# 01_Power_Control.net
KiCad netlist of a schematic drawn in Altium Designer
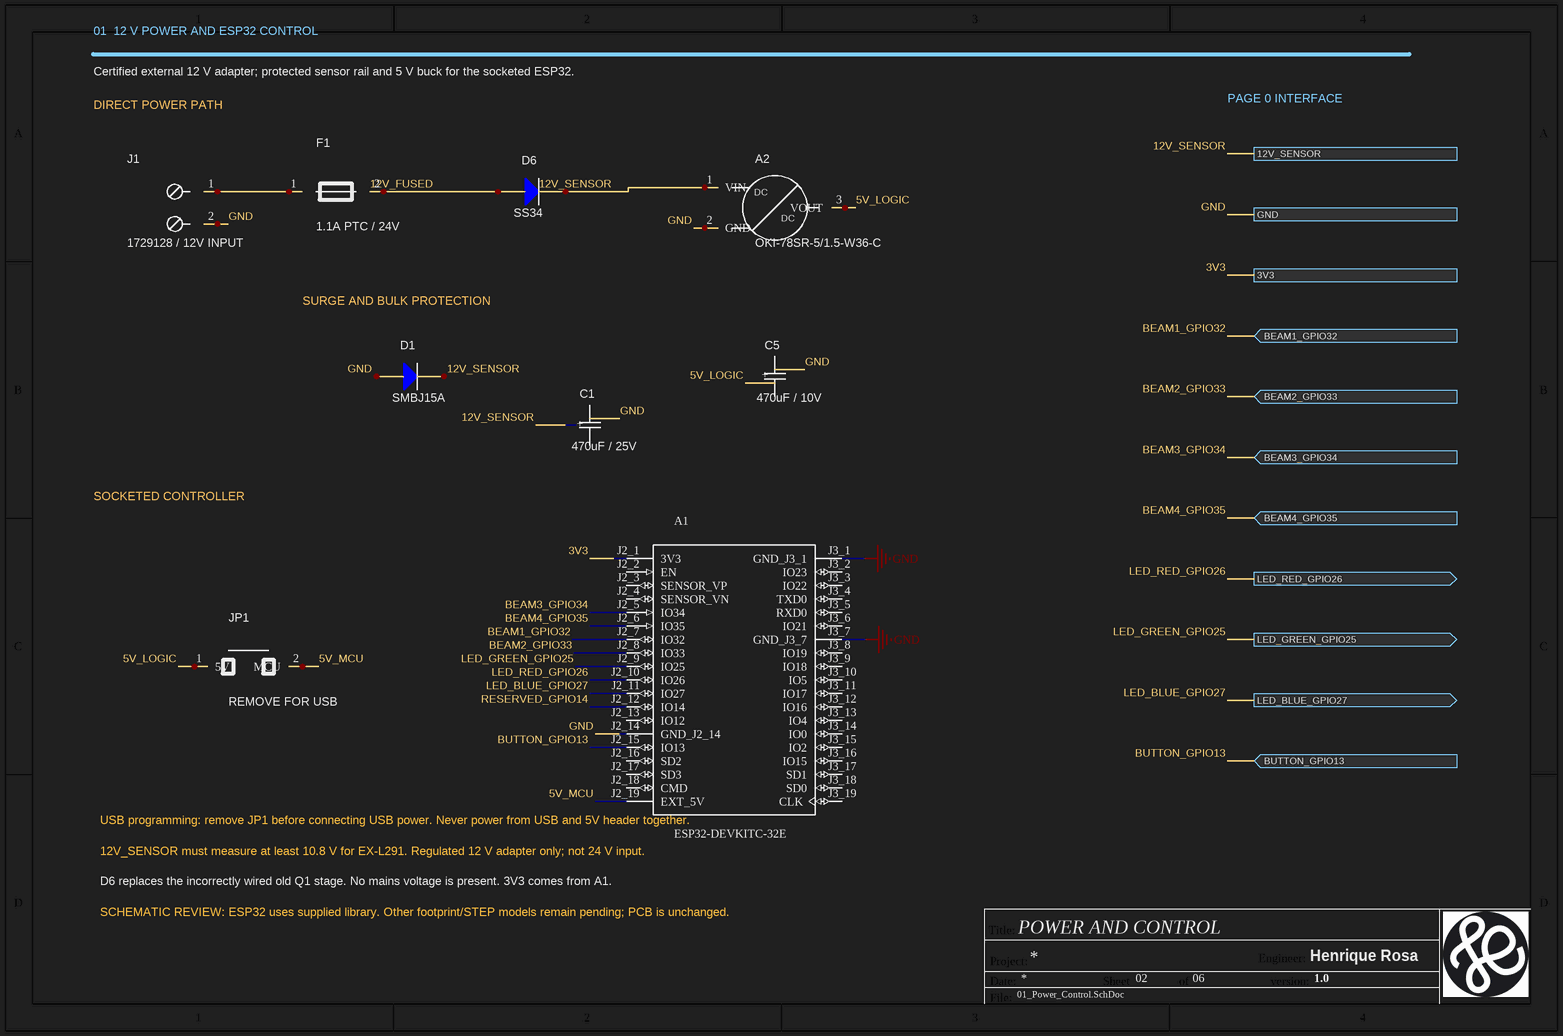
[diagram p0: 01_Power_Control.SchDoc]

(export (version "E")
  (design (tool "Eeschema 10.0.6"))
  (components
    (comp (ref "A1")
      (value "ESP32-DEVKITC-32E")
      (footprint "MODULE_ESP32-DEVKITC-32E")
      (fields
        (field (name "MF") "Espressif Systems")
        (field (name "MANUFACTURER PART NUMBER") "ESP32-DevKitC-32E")
      )
      (libsource (lib "*") (part "ESP32-DEVKITC-32E"))
    )
    (comp (ref "A2")
      (value "OKI-78SR-5/1.5-W36-C")
      (footprint "PartSpecificFootprints:MURATA_OKI78SR_VERTICAL")
      (description "12 V to regulated 5 V DC/DC module")
      (fields (field (name "MANUFACTURER") "Murata"))
      (libsource (lib "PartSpecificComponents") (part "MURATA_OKI_78SR_5_1P5"))
    )
    (comp (ref "C1")
      (value "470uF / 25V")
      (footprint "PinRepairFootprints:PANASONIC_EEUFR1E471_D10_P5")
      (description "Protected 12 V bulk capacitor")
      (fields
        (field (name "MANUFACTURER") "Panasonic")
        (field (name "MANUFACTURER PART NUMBER") "EEU-FR1E471")
      )
      (libsource (lib "Miscellaneous Devices") (part "EEU-FR1E471"))
    )
    (comp (ref "C5")
      (value "470uF / 10V")
      (footprint "PinRepairFootprints:PANASONIC_EEUFR1A471_D8_P3_5")
      (description "ESP32 Wi-Fi peak-current reservoir")
      (fields
        (field (name "MANUFACTURER") "Panasonic")
        (field (name "MANUFACTURER PART NUMBER") "EEU-FR1A471")
      )
      (libsource (lib "Miscellaneous Devices") (part "EEU-FR1A471"))
    )
    (comp (ref "D1")
      (value "SMBJ15A")
      (footprint "PinRepairFootprints:SMBJ15A_A1_K2")
      (description "15 V TVS suppressor - cathode to positive rail")
      (fields (field (name "PART NUMBER") "FDLL4148") (field (name "MANUFACTURER") "Littelfuse"))
      (libsource (lib "Miscellaneous Devices") (part "SMBJ15A"))
    )
    (comp (ref "D6")
      (value "SS34")
      (footprint "PinRepairFootprints:SS34_A1_K2")
      (description "Series reverse-polarity Schottky diode")
      (fields (field (name "PART NUMBER") "FDLL4148") (field (name "MANUFACTURER") "Vishay"))
      (libsource (lib "Miscellaneous Devices") (part "SS34-E3/57T"))
    )
    (comp (ref "F1")
      (value "1.1A PTC / 24V")
      (footprint "PinRepairFootprints:BOURNS_MFMSMF110_24X_STYLE2")
      (description "Resettable 12 V input fuse")
      (fields
        (field (name "MANUFACTURER") "Bourns")
        (field (name "MANUFACTURER PART NUMBER") "MF-MSMF110/24X-2")
      )
      (libsource (lib "*") (part "MF-MSMF110/24X-2"))
    )
    (comp (ref "J1")
      (value "1729128 / 12V INPUT")
      (footprint "PartSpecificFootprints:PHOENIX_1729128_MKDSN_2_508")
      (description "Two-position 5.08 mm screw terminal")
      (fields
        (field (name "MANUFACTURER") "Phoenix Contact")
        (field (name "MANUFACTURER PART NUMBER") "1729128")
      )
      (libsource (lib "PartSpecificComponents") (part "PHOENIX_1729128"))
    )
    (comp (ref "JP1")
      (value "REMOVE FOR USB")
      (footprint "PinRepairFootprints:SAMTEC_TSW102_07_SINGLE")
      (description "External 5 V disconnect; fit shunt only without USB")
      (fields
        (field (name "MANUFACTURER") "Samtec")
        (field (name "MANUFACTURER PART NUMBER") "TSW-102-07-G-S")
      )
      (libsource (lib "*") (part "TSW-102-07-G-S"))
    )
  )
  (nets
    (net (code "1") (name "/3V3") (class "Default")
      (node (ref "A1") (pin "J2_1") (pinfunction "3V3_J2_1") (pintype "power_in"))
    )
    (net (code "2") (name "/5V_LOGIC") (class "Default")
      (node (ref "A2") (pin "3") (pinfunction "VOUT_3") (pintype "passive"))
      (node (ref "JP1") (pin "1") (pinfunction "5V_1") (pintype "passive"))
    )
    (net (code "3") (name "/5V_MCU") (class "Default")
      (node (ref "A1") (pin "J2_19") (pinfunction "EXT_5V_J2_19") (pintype "power_in"))
      (node (ref "JP1") (pin "2") (pinfunction "MCU_2") (pintype "passive"))
    )
    (net (code "4") (name "/12V_FUSED") (class "Default")
      (node (ref "D6") (pin "1") (pinfunction "A_1") (pintype "passive"))
      (node (ref "F1") (pin "2") (pintype "passive"))
    )
    (net (code "5") (name "/12V_SENSOR") (class "Default")
      (node (ref "A2") (pin "1") (pinfunction "VIN_1") (pintype "passive"))
      (node (ref "D1") (pin "2") (pinfunction "K_2") (pintype "passive"))
      (node (ref "D6") (pin "2") (pinfunction "K_2") (pintype "passive"))
    )
    (net (code "6") (name "/BEAM1_GPIO32") (class "Default")
      (node (ref "A1") (pin "J2_7") (pinfunction "IO32_J2_7") (pintype "bidirectional"))
    )
    (net (code "7") (name "/BEAM2_GPIO33") (class "Default")
      (node (ref "A1") (pin "J2_8") (pinfunction "IO33_J2_8") (pintype "bidirectional"))
    )
    (net (code "8") (name "/BEAM3_GPIO34") (class "Default")
      (node (ref "A1") (pin "J2_5") (pinfunction "IO34_J2_5") (pintype "input"))
    )
    (net (code "9") (name "/BEAM4_GPIO35") (class "Default")
      (node (ref "A1") (pin "J2_6") (pinfunction "IO35_J2_6") (pintype "input"))
    )
    (net (code "10") (name "/BUTTON_GPIO13") (class "Default")
      (node (ref "A1") (pin "J2_15") (pinfunction "IO13_J2_15") (pintype "bidirectional"))
    )
    (net (code "11") (name "/LED_BLUE_GPIO27") (class "Default")
      (node (ref "A1") (pin "J2_11") (pinfunction "IO27_J2_11") (pintype "bidirectional"))
    )
    (net (code "12") (name "/LED_GREEN_GPIO25") (class "Default")
      (node (ref "A1") (pin "J2_9") (pinfunction "IO25_J2_9") (pintype "bidirectional"))
    )
    (net (code "13") (name "/LED_RED_GPIO26") (class "Default")
      (node (ref "A1") (pin "J2_10") (pinfunction "IO26_J2_10") (pintype "bidirectional"))
    )
    (net (code "14") (name "/RESERVED_GPIO14") (class "Default")
      (node (ref "A1") (pin "J2_12") (pinfunction "IO14_J2_12") (pintype "bidirectional"))
    )
    (net (code "15") (name "GND") (class "Default")
      (node (ref "A1") (pin "J2_14") (pinfunction "GND_J2_14_J2_14") (pintype "power_in"))
      (node (ref "A1") (pin "J3_1") (pinfunction "GND_J3_1_J3_1") (pintype "power_in"))
      (node (ref "A1") (pin "J3_7") (pinfunction "GND_J3_7_J3_7") (pintype "power_in"))
      (node (ref "A2") (pin "2") (pinfunction "GND_2") (pintype "passive"))
      (node (ref "D1") (pin "1") (pinfunction "A_1") (pintype "passive"))
      (node (ref "J1") (pin "2") (pinfunction "0V_2") (pintype "power_in"))
    )
    (net (code "16") (name "Net-(J1-+12V)") (class "Default")
      (node (ref "F1") (pin "1") (pintype "passive"))
      (node (ref "J1") (pin "1") (pinfunction "+12V_1") (pintype "power_in"))
    )
    (net (code "17") (name "unconnected-(A1-CLK-PadJ3_19)") (class "Default")
      (node (ref "A1") (pin "J3_19") (pinfunction "CLK_J3_19") (pintype "bidirectional"))
    )
    (net (code "18") (name "unconnected-(A1-CMD-PadJ2_18)") (class "Default")
      (node (ref "A1") (pin "J2_18") (pinfunction "CMD_J2_18") (pintype "bidirectional"))
    )
    (net (code "19") (name "unconnected-(A1-EN-PadJ2_2)") (class "Default")
      (node (ref "A1") (pin "J2_2") (pinfunction "EN_J2_2") (pintype "input"))
    )
    (net (code "20") (name "unconnected-(A1-IO0-PadJ3_14)") (class "Default")
      (node (ref "A1") (pin "J3_14") (pinfunction "IO0_J3_14") (pintype "bidirectional"))
    )
    (net (code "21") (name "unconnected-(A1-IO2-PadJ3_15)") (class "Default")
      (node (ref "A1") (pin "J3_15") (pinfunction "IO2_J3_15") (pintype "bidirectional"))
    )
    (net (code "22") (name "unconnected-(A1-IO4-PadJ3_13)") (class "Default")
      (node (ref "A1") (pin "J3_13") (pinfunction "IO4_J3_13") (pintype "bidirectional"))
    )
    (net (code "23") (name "unconnected-(A1-IO5-PadJ3_10)") (class "Default")
      (node (ref "A1") (pin "J3_10") (pinfunction "IO5_J3_10") (pintype "bidirectional"))
    )
    (net (code "24") (name "unconnected-(A1-IO12-PadJ2_13)") (class "Default")
      (node (ref "A1") (pin "J2_13") (pinfunction "IO12_J2_13") (pintype "bidirectional"))
    )
    (net (code "25") (name "unconnected-(A1-IO15-PadJ3_16)") (class "Default")
      (node (ref "A1") (pin "J3_16") (pinfunction "IO15_J3_16") (pintype "bidirectional"))
    )
    (net (code "26") (name "unconnected-(A1-IO16-PadJ3_12)") (class "Default")
      (node (ref "A1") (pin "J3_12") (pinfunction "IO16_J3_12") (pintype "bidirectional"))
    )
    (net (code "27") (name "unconnected-(A1-IO17-PadJ3_11)") (class "Default")
      (node (ref "A1") (pin "J3_11") (pinfunction "IO17_J3_11") (pintype "bidirectional"))
    )
    (net (code "28") (name "unconnected-(A1-IO18-PadJ3_9)") (class "Default")
      (node (ref "A1") (pin "J3_9") (pinfunction "IO18_J3_9") (pintype "bidirectional"))
    )
    (net (code "29") (name "unconnected-(A1-IO19-PadJ3_8)") (class "Default")
      (node (ref "A1") (pin "J3_8") (pinfunction "IO19_J3_8") (pintype "bidirectional"))
    )
    (net (code "30") (name "unconnected-(A1-IO21-PadJ3_6)") (class "Default")
      (node (ref "A1") (pin "J3_6") (pinfunction "IO21_J3_6") (pintype "bidirectional"))
    )
    (net (code "31") (name "unconnected-(A1-IO22-PadJ3_3)") (class "Default")
      (node (ref "A1") (pin "J3_3") (pinfunction "IO22_J3_3") (pintype "bidirectional"))
    )
    (net (code "32") (name "unconnected-(A1-IO23-PadJ3_2)") (class "Default")
      (node (ref "A1") (pin "J3_2") (pinfunction "IO23_J3_2") (pintype "bidirectional"))
    )
    (net (code "33") (name "unconnected-(A1-RXD0-PadJ3_5)") (class "Default")
      (node (ref "A1") (pin "J3_5") (pinfunction "RXD0_J3_5") (pintype "bidirectional"))
    )
    (net (code "34") (name "unconnected-(A1-SD0-PadJ3_18)") (class "Default")
      (node (ref "A1") (pin "J3_18") (pinfunction "SD0_J3_18") (pintype "bidirectional"))
    )
    (net (code "35") (name "unconnected-(A1-SD1-PadJ3_17)") (class "Default")
      (node (ref "A1") (pin "J3_17") (pinfunction "SD1_J3_17") (pintype "bidirectional"))
    )
    (net (code "36") (name "unconnected-(A1-SD2-PadJ2_16)") (class "Default")
      (node (ref "A1") (pin "J2_16") (pinfunction "SD2_J2_16") (pintype "bidirectional"))
    )
    (net (code "37") (name "unconnected-(A1-SD3-PadJ2_17)") (class "Default")
      (node (ref "A1") (pin "J2_17") (pinfunction "SD3_J2_17") (pintype "bidirectional"))
    )
    (net (code "38") (name "unconnected-(A1-SENSOR_VN-PadJ2_4)") (class "Default")
      (node (ref "A1") (pin "J2_4") (pinfunction "SENSOR_VN_J2_4") (pintype "bidirectional"))
    )
    (net (code "39") (name "unconnected-(A1-SENSOR_VP-PadJ2_3)") (class "Default")
      (node (ref "A1") (pin "J2_3") (pinfunction "SENSOR_VP_J2_3") (pintype "bidirectional"))
    )
    (net (code "40") (name "unconnected-(A1-TXD0-PadJ3_4)") (class "Default")
      (node (ref "A1") (pin "J3_4") (pinfunction "TXD0_J3_4") (pintype "bidirectional"))
    )
    (net (code "41") (name "unconnected-(C1-Pad1)") (class "Default")
      (node (ref "C1") (pin "1") (pinfunction "1_1") (pintype "passive"))
    )
    (net (code "42") (name "unconnected-(C1-Pad2)") (class "Default")
      (node (ref "C1") (pin "2") (pinfunction "2_2") (pintype "passive"))
    )
    (net (code "43") (name "unconnected-(C5-Pad1)") (class "Default")
      (node (ref "C5") (pin "1") (pinfunction "1_1") (pintype "passive"))
    )
    (net (code "44") (name "unconnected-(C5-Pad2)") (class "Default")
      (node (ref "C5") (pin "2") (pinfunction "2_2") (pintype "passive"))
    )
  )
)
